# 2_ESP32.net
KiCad netlist of a schematic drawn in Altium Designer
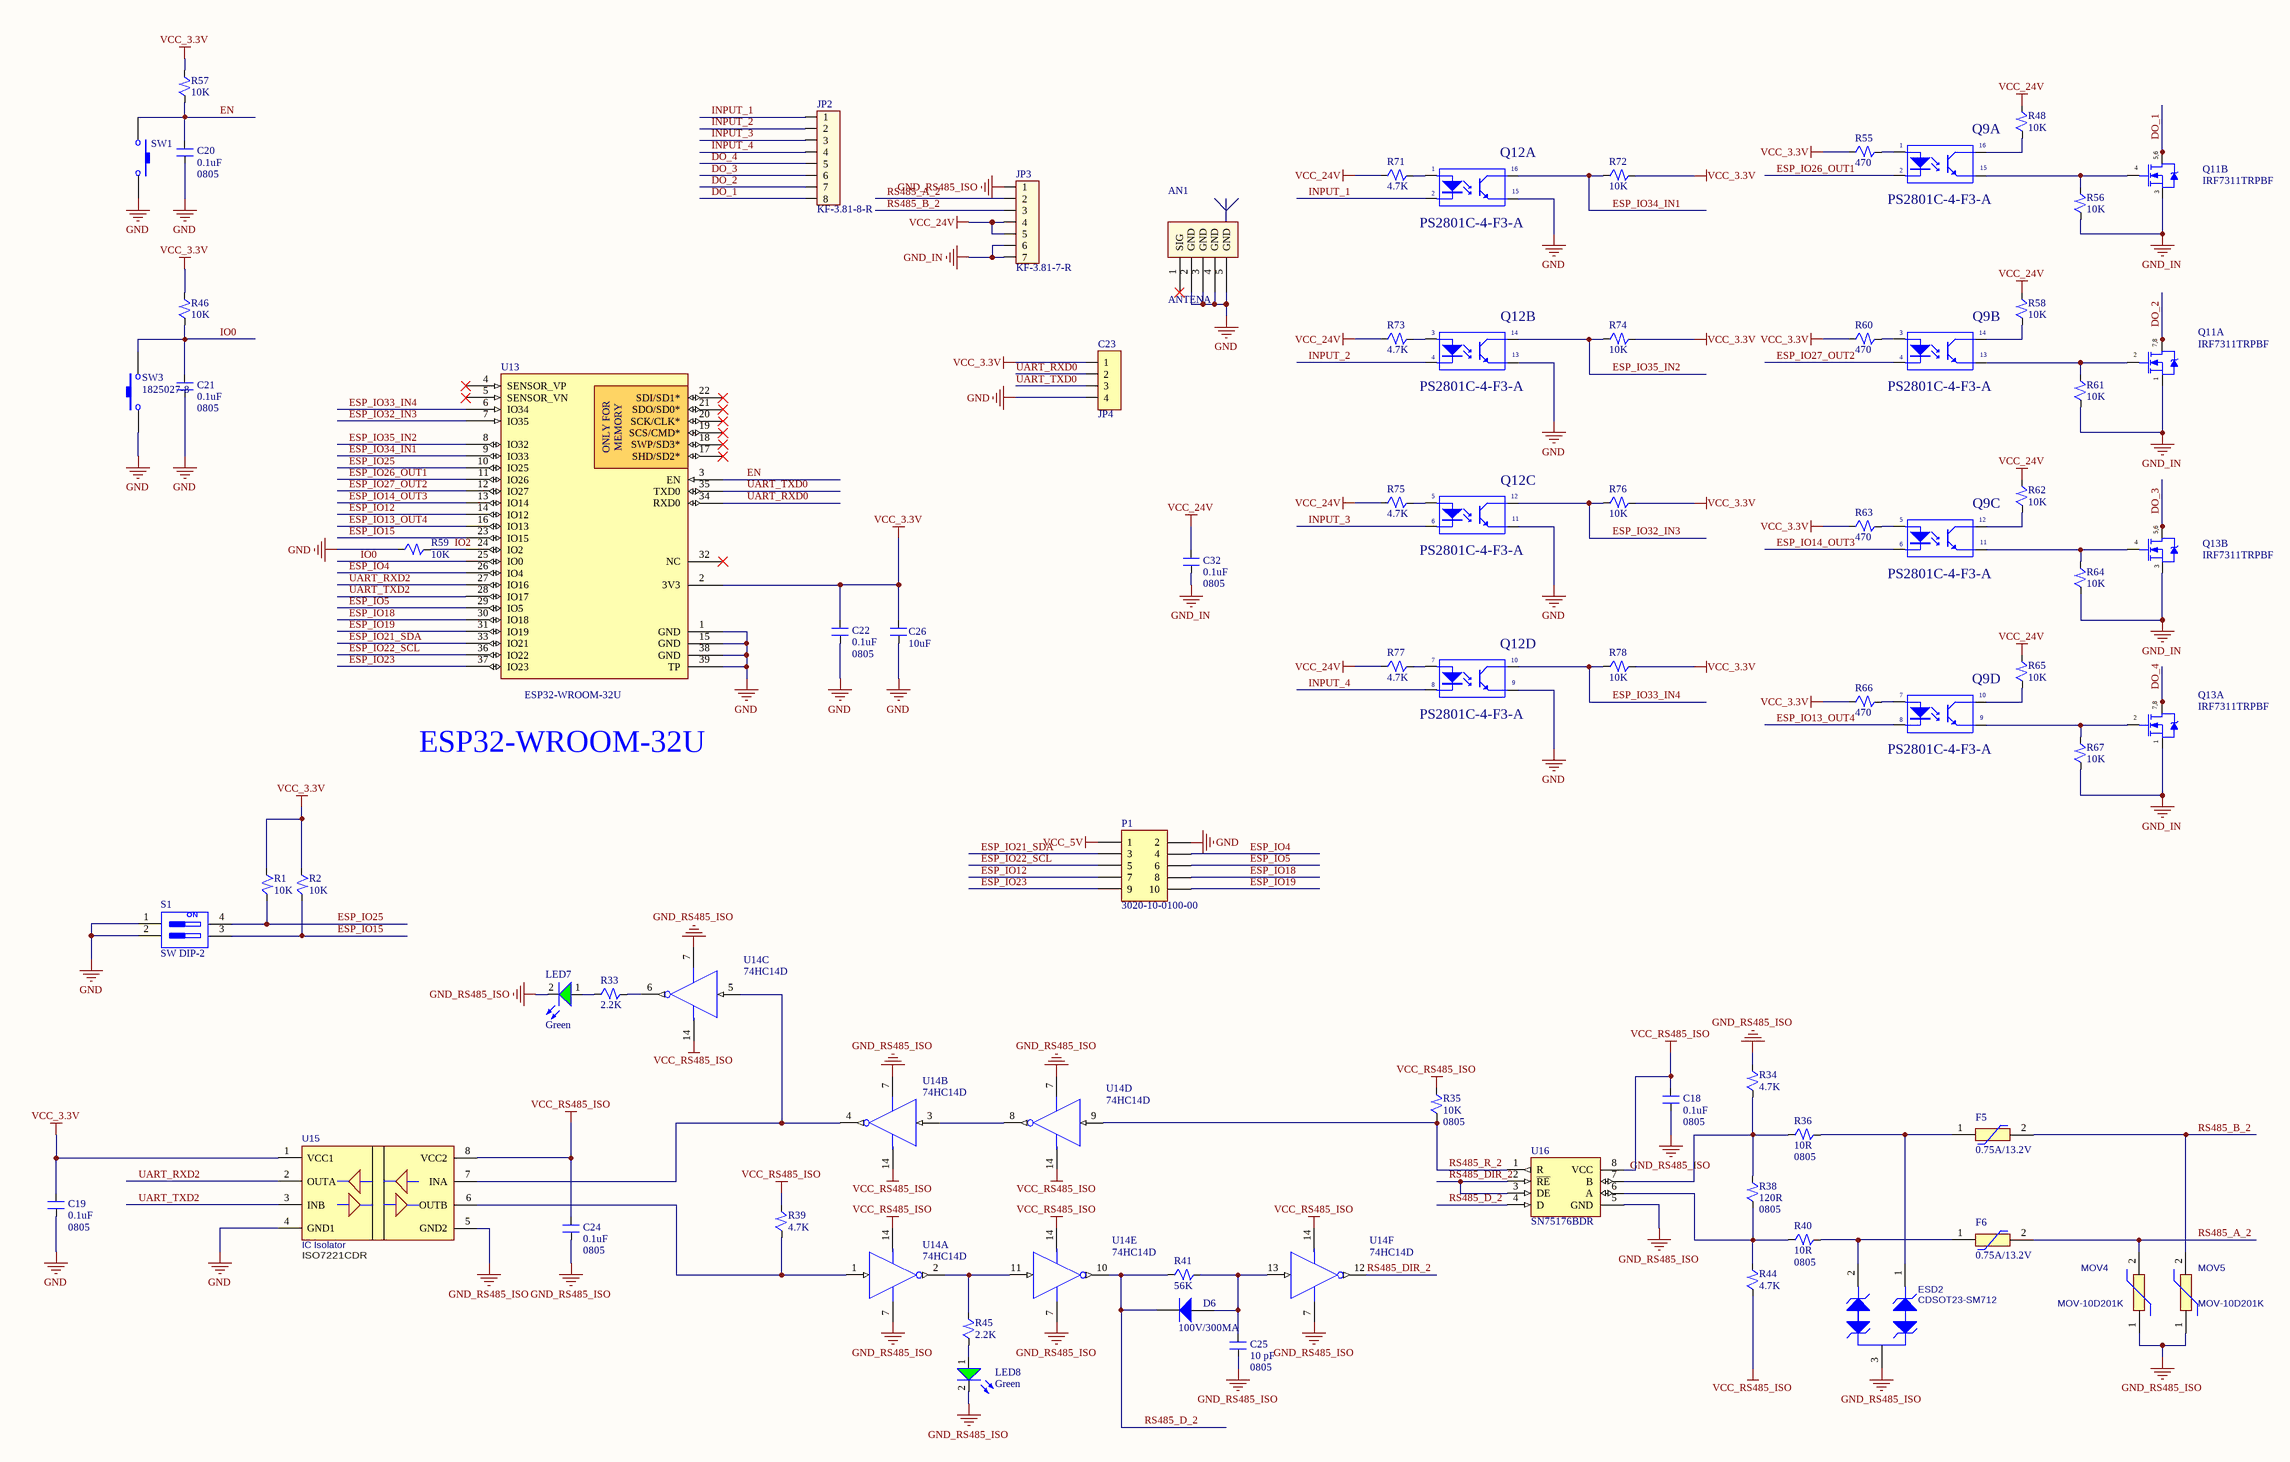
[diagram p0: [2] ESP32.SchDoc]

(export (version "E")
  (design (tool "Eeschema 10.0.6"))
  (components
    (comp (ref "AN1")
      (value "ANTENA")
      (footprint "DE ANTEN SMA CONG")
      (description "Generic Antenna")
      (libsource (lib "DIEN TU HELLO") (part "ANTEN SMA CONG"))
    )
    (comp (ref "C18")
      (value "0.1uF")
      (footprint "CN-SMD-0805")
      (description "CAP CER 0.1UF 50V 0805")
      (fields (field (name "PACKAGE") "0805") (field (name "TOLERANCE") "10%") (field (name "VOLTAGE") "50V"))
      (libsource (lib "DIEN TU HELLO") (part "CAP 0.1uF 0805 10% 50V"))
    )
    (comp (ref "C19")
      (value "0.1uF")
      (footprint "CN-SMD-0805")
      (description "CAP CER 0.1UF 50V 0805")
      (fields (field (name "PACKAGE") "0805") (field (name "TOLERANCE") "10%") (field (name "VOLTAGE") "50V"))
      (libsource (lib "DIEN TU HELLO") (part "CAP 0.1uF 0805 10% 50V"))
    )
    (comp (ref "C20")
      (value "0.1uF")
      (footprint "CN-SMD-0805")
      (description "CAP CER 0.1UF 50V 0805")
      (fields (field (name "PACKAGE") "0805") (field (name "TOLERANCE") "10%") (field (name "VOLTAGE") "50V"))
      (libsource (lib "DIEN TU HELLO") (part "CAP 0.1uF 0805 10% 50V"))
    )
    (comp (ref "C21")
      (value "0.1uF")
      (footprint "CN-SMD-0805")
      (description "CAP CER 0.1UF 50V 0805")
      (fields (field (name "PACKAGE") "0805") (field (name "TOLERANCE") "10%") (field (name "VOLTAGE") "50V"))
      (libsource (lib "DIEN TU HELLO") (part "CAP 0.1uF 0805 10% 50V"))
    )
    (comp (ref "C22")
      (value "0.1uF")
      (footprint "CN-SMD-0805")
      (description "CAP CER 0.1UF 50V 0805")
      (fields (field (name "PACKAGE") "0805") (field (name "TOLERANCE") "10%") (field (name "VOLTAGE") "50V"))
      (libsource (lib "DIEN TU HELLO") (part "CAP 0.1uF 0805 10% 50V"))
    )
    (comp (ref "C23")
      (value "JP4")
      (footprint "JP4-C1T")
      (description "WR-PHD 2.54 mm Angled Socket Header")
      (fields
        (field (name "MANUFACTURER") "Würth Elektronik eiSos GmbH")
        (field (name "PARTNO") "613004143121")
        (field (name "CREATED BY") "Karrer Zheng")
      )
      (libsource (lib "LIBRARY") (part "JP4"))
    )
    (comp (ref "C24")
      (value "0.1uF")
      (footprint "CN-SMD-0805")
      (description "CAP CER 0.1UF 50V 0805")
      (fields (field (name "PACKAGE") "0805") (field (name "TOLERANCE") "10%") (field (name "VOLTAGE") "50V"))
      (libsource (lib "DIEN TU HELLO") (part "CAP 0.1uF 0805 10% 50V"))
    )
    (comp (ref "C25")
      (value "10 pF")
      (footprint "CN-SMD-0805")
      (description "CAP CER 0.1UF 50V 0805")
      (fields (field (name "PACKAGE") "0805") (field (name "TOLERANCE") "10%") (field (name "VOLTAGE") "50V"))
      (libsource (lib "DIEN TU HELLO") (part "CAP 0.1uF 0805 10% 50V"))
    )
    (comp (ref "C26")
      (value "10uF")
      (footprint "CN-SMD-0805")
      (description "CAP CER 10UF 16V 0805")
      (fields (field (name "TOLERANCE") "10%") (field (name "VOLTAGE") "16V"))
      (libsource (lib "DIEN TU HELLO") (part "CAP 10uF 0805 10% 16V"))
    )
    (comp (ref "C32")
      (value "0.1uF")
      (footprint "CN-SMD-0805")
      (description "CAP CER 0.1UF 50V 0805")
      (fields (field (name "PACKAGE") "0805") (field (name "TOLERANCE") "10%") (field (name "VOLTAGE") "50V"))
      (libsource (lib "DIEN TU HELLO") (part "CAP 0.1uF 0805 10% 50V"))
    )
    (comp (ref "D6")
      (value "100V/300MA")
      (footprint "SOD-123")
      (description "DIODE GEN PURP 100V 300MA SOD123")
      (fields (field (name "PART NUMBER") "1N4148W-7-F") (field (name "MANUFACTURER") "Diodes Incorporated"))
      (libsource (lib "DIEN TU HELLO") (part "1N4148-W-7"))
    )
    (comp (ref "ESD2")
      (value "CDSOT23-SM712")
      (footprint "SOT-323_ESD")
      (fields (field (name "MANUFACTURER") "Bourns"))
      (libsource (lib "DIEN TU HELLO") (part "CDSOT23-SM712"))
    )
    (comp (ref "F5")
      (value "0.75A/13.2V")
      (footprint "MINISMDC050F2")
      (description "PTC RESET FUSE 13.2V 750MA 1812")
      (fields (field (name "MANUFACTURER") "LITTELFUSE") (field (name "PART NUMBER") "MINISMDC075F-2"))
      (libsource (lib "DIEN TU HELLO") (part "MINISMDC075F-2"))
    )
    (comp (ref "F6")
      (value "0.75A/13.2V")
      (footprint "MINISMDC050F2")
      (description "PTC RESET FUSE 13.2V 750MA 1812")
      (fields (field (name "MANUFACTURER") "LITTELFUSE") (field (name "PART NUMBER") "MINISMDC075F-2"))
      (libsource (lib "DIEN TU HELLO") (part "MINISMDC075F-2"))
    )
    (comp (ref "JP2")
      (value "KF-3.81-8-R")
      (footprint "KF-3.81-8-R")
      (description "Terminal Block Plug-in Hàn PCB Chân Cong 3.81mm")
      (libsource (lib "DIEN TU HELLO") (part "Con_8C"))
    )
    (comp (ref "JP3")
      (value "KF-3.81-7-R")
      (footprint "KF-3.81-7-R")
      (description "Terminal Block Plug-in Hàn PCB Chân Cong 3.81mm")
      (libsource (lib "DIEN TU HELLO") (part "Con_7C"))
    )
    (comp (ref "LED7")
      (value "Green")
      (footprint "LED5G")
      (description "LED Green 5mm")
      (fields (field (name "Comment") "LED_G_5"))
      (libsource (lib "DIEN TU HELLO") (part "LED_GREEN_5MM"))
    )
    (comp (ref "LED8")
      (value "Green")
      (footprint "LED5G")
      (description "LED Green 5mm")
      (fields (field (name "Comment") "LED_G_5"))
      (libsource (lib "DIEN TU HELLO") (part "LED_GREEN_5MM"))
    )
    (comp (ref "MOV4")
      (value "MOV-10D201K")
      (footprint "MOV10D201KTR")
      (description "MOV 225V 250pF 340V Clamp Voltage 2.5 kA 10%")
      (fields (field (name "MANUFACTURER") "Bourns"))
      (libsource (lib "DIEN TU HELLO") (part "MOV-10D201K"))
    )
    (comp (ref "MOV5")
      (value "MOV-10D201K")
      (footprint "MOV10D201KTR")
      (description "MOV 225V 250pF 340V Clamp Voltage 2.5 kA 10%")
      (fields (field (name "MANUFACTURER") "Bourns"))
      (libsource (lib "DIEN TU HELLO") (part "MOV-10D201K"))
    )
    (comp (ref "P1")
      (value "3020-10-0100-00")
      (footprint "IDC_HDR_M_2X5_2.54_THG")
      (description "IDC BOX HEADER .100\" 10POS")
      (fields (field (name "MANUFACTURER") "CNC Tech"))
      (libsource (lib "Indruino") (part "IDC_HDR_M_3020-10-0100-00"))
    )
    (comp (ref "Q9")
      (value "PS2801C-4-F3-A")
      (footprint "PS2801C-4_REN-L")
      (fields (field (name "MANUFACTURER") "Renesas Electronics"))
      (libsource (lib "DIEN TU HELLO") (part "PS2801C-4_MH"))
    )
    (comp (ref "Q11")
      (value "IRF7311TRPBF")
      (footprint "SO8")
      (description "MOSFET N-2CH 6.6A 20V 29mOhm 8-SOIC")
      (fields
        (field (name "MANUFACTURER") "Infineon Technologies")
        (field (name "PUBLISHER") "Altium Limited")
      )
      (libsource (lib "DIEN TU HELLO") (part "IRF7311TRPBF"))
    )
    (comp (ref "Q12")
      (value "PS2801C-4-F3-A")
      (footprint "PS2801C-4_REN-L")
      (fields (field (name "MANUFACTURER") "Renesas Electronics"))
      (libsource (lib "DIEN TU HELLO") (part "PS2801C-4_MH"))
    )
    (comp (ref "Q13")
      (value "IRF7311TRPBF")
      (footprint "SO8")
      (description "MOSFET N-2CH 6.6A 20V 29mOhm 8-SOIC")
      (fields
        (field (name "MANUFACTURER") "Infineon Technologies")
        (field (name "PUBLISHER") "Altium Limited")
      )
      (libsource (lib "DIEN TU HELLO") (part "IRF7311TRPBF"))
    )
    (comp (ref "R1")
      (value "10K")
      (footprint "RES_0805")
      (description "Điện Trở 10 KOhm 0805 1% 1/8W")
      (fields (field (name "PART NUMBER") "Trở 0805 1% 10K") (field (name "MANUFACTURER") "Minh Hà"))
      (libsource (lib "DIEN TU HELLO") (part "RES 10K 0805 1% 1/8W"))
    )
    (comp (ref "R2")
      (value "10K")
      (footprint "RES_0805")
      (description "Điện Trở 10 KOhm 0805 1% 1/8W")
      (fields (field (name "PART NUMBER") "Trở 0805 1% 10K") (field (name "MANUFACTURER") "Minh Hà"))
      (libsource (lib "DIEN TU HELLO") (part "RES 10K 0805 1% 1/8W"))
    )
    (comp (ref "R33")
      (value "2.2K")
      (footprint "RES_0805")
      (description "Điện Trở 2.2 KOhm 0805 1% 1/8W")
      (fields (field (name "PART NUMBER") "Trở 0805 1% 2.2K") (field (name "MANUFACTURER") "Minh Hà"))
      (libsource (lib "DIEN TU HELLO") (part "RES 2.2K 0805 1% 1/8W"))
    )
    (comp (ref "R34")
      (value "4.7K")
      (footprint "RES_0805")
      (description "Điện Trở 4.7 KOhm 0805 1% 1/8W")
      (fields (field (name "PART NUMBER") "Trở 0805 1% 4.7K") (field (name "MANUFACTURER") "Minh Hà"))
      (libsource (lib "DIEN TU HELLO") (part "RES 4.7K 0805 1% 1/8W"))
    )
    (comp (ref "R35")
      (value "10K")
      (footprint "RES_0805")
      (description "Điện Trở 10 KOhm 0805 1% 1/8W")
      (fields
        (field (name "PART NUMBER") "Trở 0805 1% 10K")
        (field (name "MANUFACTURER") "Minh Hà")
        (field (name "PACKAGE") "0805")
      )
      (libsource (lib "DIEN TU HELLO") (part "RES 10K 0805 1% 1/8W"))
    )
    (comp (ref "R36")
      (value "10R")
      (footprint "RES_0805")
      (description "Điện Trở 10 Ohm 0805 1% 1/8W")
      (fields
        (field (name "PART NUMBER") "Trở 0805 1% 10R")
        (field (name "MANUFACTURER") "Minh Hà")
        (field (name "PACKAGE") "0805")
      )
      (libsource (lib "DIEN TU HELLO") (part "RES 10R 0805 1% 1/8W"))
    )
    (comp (ref "R38")
      (value "120R")
      (footprint "RES_0805")
      (description "Điện Trở 120 Ohm 0805 1% 1/8W")
      (fields
        (field (name "PART NUMBER") "Trở 0805 1% 120R")
        (field (name "MANUFACTURER") "Minh Hà")
        (field (name "PACKAGE") "0805")
      )
      (libsource (lib "DIEN TU HELLO") (part "RES 120R 0805 1% 1/8W"))
    )
    (comp (ref "R39")
      (value "4.7K")
      (footprint "RES_0805")
      (description "Điện Trở 4.7 KOhm 0805 1% 1/8W")
      (fields (field (name "PART NUMBER") "Trở 0805 1% 4.7K") (field (name "MANUFACTURER") "Minh Hà"))
      (libsource (lib "DIEN TU HELLO") (part "RES 4.7K 0805 1% 1/8W"))
    )
    (comp (ref "R40")
      (value "10R")
      (footprint "RES_0805")
      (description "Điện Trở 10 Ohm 0805 1% 1/8W")
      (fields
        (field (name "PART NUMBER") "Trở 0805 1% 10R")
        (field (name "MANUFACTURER") "Minh Hà")
        (field (name "PACKAGE") "0805")
      )
      (libsource (lib "DIEN TU HELLO") (part "RES 10R 0805 1% 1/8W"))
    )
    (comp (ref "R41")
      (value "56K")
      (footprint "RES_0805")
      (description "Điện Trở 56 KOhm 0805 5% 1/8W")
      (fields (field (name "PART NUMBER") "Trở 0805 5% 56K") (field (name "MANUFACTURER") "Thế Giới IC"))
      (libsource (lib "DIEN TU HELLO") (part "RES 56K 0805 5% 1/8W"))
    )
    (comp (ref "R44")
      (value "4.7K")
      (footprint "RES_0805")
      (description "Điện Trở 4.7 KOhm 0805 1% 1/8W")
      (fields (field (name "PART NUMBER") "Trở 0805 1% 4.7K") (field (name "MANUFACTURER") "Minh Hà"))
      (libsource (lib "DIEN TU HELLO") (part "RES 4.7K 0805 1% 1/8W"))
    )
    (comp (ref "R45")
      (value "2.2K")
      (footprint "RES_0805")
      (description "Điện Trở 2.2 KOhm 0805 1% 1/8W")
      (fields (field (name "PART NUMBER") "Trở 0805 1% 2.2K") (field (name "MANUFACTURER") "Minh Hà"))
      (libsource (lib "DIEN TU HELLO") (part "RES 2.2K 0805 1% 1/8W"))
    )
    (comp (ref "R46")
      (value "10K")
      (footprint "RES_0805")
      (description "Điện Trở 10 KOhm 0805 1% 1/8W")
      (fields (field (name "PART NUMBER") "Trở 0805 1% 10K") (field (name "MANUFACTURER") "Minh Hà"))
      (libsource (lib "DIEN TU HELLO") (part "RES 10K 0805 1% 1/8W"))
    )
    (comp (ref "R48")
      (value "10K")
      (footprint "RES_0805")
      (description "Điện Trở 10 KOhm 0805 1% 1/8W")
      (fields (field (name "PART NUMBER") "Trở 0805 1% 10K") (field (name "MANUFACTURER") "Minh Hà"))
      (libsource (lib "DIEN TU HELLO") (part "RES 10K 0805 1% 1/8W"))
    )
    (comp (ref "R55")
      (value "470")
      (footprint "RES_0805")
      (description "Điện Trở 470 Ohm 0805 1% 1/8W")
      (fields (field (name "PART NUMBER") "Trở 0805 1% 470R") (field (name "MANUFACTURER") "Minh Hà"))
      (libsource (lib "DIEN TU HELLO") (part "RES 470R 0805 1% 1/8W"))
    )
    (comp (ref "R56")
      (value "10K")
      (footprint "RES_0805")
      (description "Điện Trở 10 KOhm 0805 1% 1/8W")
      (fields (field (name "PART NUMBER") "Trở 0805 1% 10K") (field (name "MANUFACTURER") "Minh Hà"))
      (libsource (lib "DIEN TU HELLO") (part "RES 10K 0805 1% 1/8W"))
    )
    (comp (ref "R57")
      (value "10K")
      (footprint "RES_0805")
      (description "Điện Trở 10 KOhm 0805 1% 1/8W")
      (fields (field (name "PART NUMBER") "Trở 0805 1% 10K") (field (name "MANUFACTURER") "Minh Hà"))
      (libsource (lib "DIEN TU HELLO") (part "RES 10K 0805 1% 1/8W"))
    )
    (comp (ref "R58")
      (value "10K")
      (footprint "RES_0805")
      (description "Điện Trở 10 KOhm 0805 1% 1/8W")
      (fields (field (name "PART NUMBER") "Trở 0805 1% 10K") (field (name "MANUFACTURER") "Minh Hà"))
      (libsource (lib "DIEN TU HELLO") (part "RES 10K 0805 1% 1/8W"))
    )
    (comp (ref "R59")
      (value "10K")
      (footprint "RES_0805")
      (description "Điện Trở 10 KOhm 0805 1% 1/8W")
      (fields (field (name "PART NUMBER") "Trở 0805 1% 10K") (field (name "MANUFACTURER") "Minh Hà"))
      (libsource (lib "DIEN TU HELLO") (part "RES 10K 0805 1% 1/8W"))
    )
    (comp (ref "R60")
      (value "470")
      (footprint "RES_0805")
      (description "Điện Trở 470 Ohm 0805 1% 1/8W")
      (fields (field (name "PART NUMBER") "Trở 0805 1% 470R") (field (name "MANUFACTURER") "Minh Hà"))
      (libsource (lib "DIEN TU HELLO") (part "RES 470R 0805 1% 1/8W"))
    )
    (comp (ref "R61")
      (value "10K")
      (footprint "RES_0805")
      (description "Điện Trở 10 KOhm 0805 1% 1/8W")
      (fields (field (name "PART NUMBER") "Trở 0805 1% 10K") (field (name "MANUFACTURER") "Minh Hà"))
      (libsource (lib "DIEN TU HELLO") (part "RES 10K 0805 1% 1/8W"))
    )
    (comp (ref "R62")
      (value "10K")
      (footprint "RES_0805")
      (description "Điện Trở 10 KOhm 0805 1% 1/8W")
      (fields (field (name "PART NUMBER") "Trở 0805 1% 10K") (field (name "MANUFACTURER") "Minh Hà"))
      (libsource (lib "DIEN TU HELLO") (part "RES 10K 0805 1% 1/8W"))
    )
    (comp (ref "R63")
      (value "470")
      (footprint "RES_0805")
      (description "Điện Trở 470 Ohm 0805 1% 1/8W")
      (fields (field (name "PART NUMBER") "Trở 0805 1% 470R") (field (name "MANUFACTURER") "Minh Hà"))
      (libsource (lib "DIEN TU HELLO") (part "RES 470R 0805 1% 1/8W"))
    )
    (comp (ref "R64")
      (value "10K")
      (footprint "RES_0805")
      (description "Điện Trở 10 KOhm 0805 1% 1/8W")
      (fields (field (name "PART NUMBER") "Trở 0805 1% 10K") (field (name "MANUFACTURER") "Minh Hà"))
      (libsource (lib "DIEN TU HELLO") (part "RES 10K 0805 1% 1/8W"))
    )
    (comp (ref "R65")
      (value "10K")
      (footprint "RES_0805")
      (description "Điện Trở 10 KOhm 0805 1% 1/8W")
      (fields (field (name "PART NUMBER") "Trở 0805 1% 10K") (field (name "MANUFACTURER") "Minh Hà"))
      (libsource (lib "DIEN TU HELLO") (part "RES 10K 0805 1% 1/8W"))
    )
    (comp (ref "R66")
      (value "470")
      (footprint "RES_0805")
      (description "Điện Trở 470 Ohm 0805 1% 1/8W")
      (fields (field (name "PART NUMBER") "Trở 0805 1% 470R") (field (name "MANUFACTURER") "Minh Hà"))
      (libsource (lib "DIEN TU HELLO") (part "RES 470R 0805 1% 1/8W"))
    )
    (comp (ref "R67")
      (value "10K")
      (footprint "RES_0805")
      (description "Điện Trở 10 KOhm 0805 1% 1/8W")
      (fields (field (name "PART NUMBER") "Trở 0805 1% 10K") (field (name "MANUFACTURER") "Minh Hà"))
      (libsource (lib "DIEN TU HELLO") (part "RES 10K 0805 1% 1/8W"))
    )
    (comp (ref "R71")
      (value "4.7K")
      (footprint "RES_0805")
      (description "Điện Trở 4.7 KOhm 0805 1% 1/8W")
      (fields (field (name "PART NUMBER") "Trở 0805 1% 4.7K") (field (name "MANUFACTURER") "Minh Hà"))
      (libsource (lib "DIEN TU HELLO") (part "RES 4.7K 0805 1% 1/8W"))
    )
    (comp (ref "R72")
      (value "10K")
      (footprint "RES_0805")
      (description "Điện Trở 10 KOhm 0805 1% 1/8W")
      (fields (field (name "PART NUMBER") "Trở 0805 1% 10K") (field (name "MANUFACTURER") "Minh Hà"))
      (libsource (lib "DIEN TU HELLO") (part "RES 10K 0805 1% 1/8W"))
    )
    (comp (ref "R73")
      (value "4.7K")
      (footprint "RES_0805")
      (description "Điện Trở 4.7 KOhm 0805 1% 1/8W")
      (fields (field (name "PART NUMBER") "Trở 0805 1% 4.7K") (field (name "MANUFACTURER") "Minh Hà"))
      (libsource (lib "DIEN TU HELLO") (part "RES 4.7K 0805 1% 1/8W"))
    )
    (comp (ref "R74")
      (value "10K")
      (footprint "RES_0805")
      (description "Điện Trở 10 KOhm 0805 1% 1/8W")
      (fields (field (name "PART NUMBER") "Trở 0805 1% 10K") (field (name "MANUFACTURER") "Minh Hà"))
      (libsource (lib "DIEN TU HELLO") (part "RES 10K 0805 1% 1/8W"))
    )
    (comp (ref "R75")
      (value "4.7K")
      (footprint "RES_0805")
      (description "Điện Trở 4.7 KOhm 0805 1% 1/8W")
      (fields (field (name "PART NUMBER") "Trở 0805 1% 4.7K") (field (name "MANUFACTURER") "Minh Hà"))
      (libsource (lib "DIEN TU HELLO") (part "RES 4.7K 0805 1% 1/8W"))
    )
    (comp (ref "R76")
      (value "10K")
      (footprint "RES_0805")
      (description "Điện Trở 10 KOhm 0805 1% 1/8W")
      (fields (field (name "PART NUMBER") "Trở 0805 1% 10K") (field (name "MANUFACTURER") "Minh Hà"))
      (libsource (lib "DIEN TU HELLO") (part "RES 10K 0805 1% 1/8W"))
    )
    (comp (ref "R77")
      (value "4.7K")
      (footprint "RES_0805")
      (description "Điện Trở 4.7 KOhm 0805 1% 1/8W")
      (fields (field (name "PART NUMBER") "Trở 0805 1% 4.7K") (field (name "MANUFACTURER") "Minh Hà"))
      (libsource (lib "DIEN TU HELLO") (part "RES 4.7K 0805 1% 1/8W"))
    )
    (comp (ref "R78")
      (value "10K")
      (footprint "RES_0805")
      (description "Điện Trở 10 KOhm 0805 1% 1/8W")
      (fields (field (name "PART NUMBER") "Trở 0805 1% 10K") (field (name "MANUFACTURER") "Minh Hà"))
      (libsource (lib "DIEN TU HELLO") (part "RES 10K 0805 1% 1/8W"))
    )
    (comp (ref "S1")
      (value "SW DIP-2")
      (footprint "MinhTien_PCBLib:DIP-SW-2-SIDE ENTRY")
      (description "DIP Switch, 2 Position, SPST")
      (fields (field (name "PUBLISHER") "Altium Limited"))
      (libsource (lib "MinhTien_SCHLib") (part "SW DIP-2"))
    )
    (comp (ref "SW1")
      (value "RS-282G05A3-SM RT")
      (footprint "SW_RS-282G05A3-SM RT")
      (description "SWITCH TACTILE SPST-NO 0.05A 12V")
      (fields (field (name "MANUFACTURER") "C&K"))
      (libsource (lib "DIEN TU HELLO") (part "SW_RS-282G05A3-SM RT"))
    )
    (comp (ref "SW3")
      (value "1825027-8")
      (footprint "SW_1825027-8")
      (description "SWITCH TACTILE SPST-NO 0.05A 24V")
      (fields (field (name "MANUFACTURER") "TE Connectivity ALCOSWITCH Switches"))
      (libsource (lib "Indruino") (part "SW_1825027-8"))
    )
    (comp (ref "U13")
      (value "ESP32-WROOM-32U")
      (footprint "ESP32-WROOM-32U")
      (description "Wi-Fi/BT BLE Module ESP32-D0WD")
      (fields (field (name "MANUFACTURER") "Espressif"))
      (libsource (lib "DIEN TU HELLO") (part "ESP32-WROOM-32U"))
    )
    (comp (ref "U14")
      (value "74HC14D")
      (footprint "SOIC-14")
      (description "IC INVERTER SCHMITT TRIGGER 6CH 6-INP")
      (fields (field (name "MANUFACTURER") "Nexperia USA Inc") (field (name "BASE PART NUMBER") "74HC14"))
      (libsource (lib "") (part "74HC14D_NXP_1"))
    )
    (comp (ref "U15")
      (value "IC Isolator")
      (footprint "8-SOIC_ISO")
      (description "IC Isolator 2.8V ~ 5.5V 2 Channels 25Mbps")
      (fields (field (name "MANUFACTURER") "Texas Instruments") (field (name "PART NUMBER") "ISO7221CDR"))
      (libsource (lib "DIEN TU HELLO") (part "ISO7221CD"))
    )
    (comp (ref "U16")
      (value "SN75176BDR")
      (footprint "SOIC-8")
      (description "IC TXRX DIFF BUSS 8SOIC")
      (fields (field (name "MANUFACTURER") "Texas Instruments") (field (name "PART NUMBER") "SN75HVD08DR"))
      (libsource (lib "DIEN TU HELLO") (part "SN75176BDR"))
    )
  )
  (nets
    (net (code "1") (name "/DO_1") (class "Default")
      (node (ref "JP2") (pin "8") (pinfunction "8_8") (pintype "passive"))
      (node (ref "Q11") (pin "5") (pinfunction "D_5") (pintype "passive"))
      (node (ref "Q11") (pin "6") (pinfunction "D_6") (pintype "passive"))
    )
    (net (code "2") (name "/DO_2") (class "Default")
      (node (ref "JP2") (pin "7") (pinfunction "7_7") (pintype "passive"))
      (node (ref "Q11") (pin "7") (pinfunction "D_7") (pintype "passive"))
      (node (ref "Q11") (pin "8") (pinfunction "D_8") (pintype "passive"))
    )
    (net (code "3") (name "/DO_3") (class "Default")
      (node (ref "JP2") (pin "6") (pinfunction "6_6") (pintype "passive"))
      (node (ref "Q13") (pin "5") (pinfunction "D_5") (pintype "passive"))
      (node (ref "Q13") (pin "6") (pinfunction "D_6") (pintype "passive"))
    )
    (net (code "4") (name "/DO_4") (class "Default")
      (node (ref "JP2") (pin "5") (pinfunction "5_5") (pintype "passive"))
      (node (ref "Q13") (pin "7") (pinfunction "D_7") (pintype "passive"))
      (node (ref "Q13") (pin "8") (pinfunction "D_8") (pintype "passive"))
    )
    (net (code "5") (name "/EN") (class "Default")
      (node (ref "C20") (pin "2") (pinfunction "2_2") (pintype "passive"))
      (node (ref "R57") (pin "1") (pinfunction "1_1") (pintype "passive"))
      (node (ref "SW1") (pin "1") (pinfunction "1_1") (pintype "passive"))
      (node (ref "U13") (pin "3") (pinfunction "EN_3") (pintype "input"))
    )
    (net (code "6") (name "/ESP_IO4") (class "Default")
      (node (ref "P1") (pin "4") (pinfunction "4_4") (pintype "passive"))
      (node (ref "U13") (pin "26") (pinfunction "IO4_26") (pintype "bidirectional"))
    )
    (net (code "7") (name "/ESP_IO5") (class "Default")
      (node (ref "P1") (pin "6") (pinfunction "6_6") (pintype "passive"))
      (node (ref "U13") (pin "29") (pinfunction "IO5_29") (pintype "bidirectional"))
    )
    (net (code "8") (name "/ESP_IO12") (class "Default")
      (node (ref "P1") (pin "7") (pinfunction "7_7") (pintype "passive"))
      (node (ref "U13") (pin "14") (pinfunction "IO12_14") (pintype "bidirectional"))
    )
    (net (code "9") (name "/ESP_IO13_OUT4") (class "Default")
      (node (ref "Q9") (pin "8") (pinfunction "8_8") (pintype "passive"))
      (node (ref "U13") (pin "16") (pinfunction "IO13_16") (pintype "bidirectional"))
    )
    (net (code "10") (name "/ESP_IO14_OUT3") (class "Default")
      (node (ref "Q9") (pin "6") (pinfunction "6_6") (pintype "passive"))
      (node (ref "U13") (pin "13") (pinfunction "IO14_13") (pintype "bidirectional"))
    )
    (net (code "11") (name "/ESP_IO15") (class "Default")
      (node (ref "R2") (pin "2") (pinfunction "2_2") (pintype "passive"))
      (node (ref "S1") (pin "3") (pinfunction "B2_3") (pintype "passive"))
      (node (ref "U13") (pin "23") (pinfunction "IO15_23") (pintype "bidirectional"))
    )
    (net (code "12") (name "/ESP_IO18") (class "Default")
      (node (ref "P1") (pin "8") (pinfunction "8_8") (pintype "passive"))
      (node (ref "U13") (pin "30") (pinfunction "IO18_30") (pintype "bidirectional"))
    )
    (net (code "13") (name "/ESP_IO19") (class "Default")
      (node (ref "P1") (pin "10") (pinfunction "10_10") (pintype "passive"))
      (node (ref "U13") (pin "31") (pinfunction "IO19_31") (pintype "bidirectional"))
    )
    (net (code "14") (name "/ESP_IO21_SDA") (class "Default")
      (node (ref "P1") (pin "3") (pinfunction "3_3") (pintype "passive"))
      (node (ref "U13") (pin "33") (pinfunction "IO21_33") (pintype "bidirectional"))
    )
    (net (code "15") (name "/ESP_IO22_SCL") (class "Default")
      (node (ref "P1") (pin "5") (pinfunction "5_5") (pintype "passive"))
      (node (ref "U13") (pin "36") (pinfunction "IO22_36") (pintype "bidirectional"))
    )
    (net (code "16") (name "/ESP_IO23") (class "Default")
      (node (ref "P1") (pin "9") (pinfunction "9_9") (pintype "passive"))
      (node (ref "U13") (pin "37") (pinfunction "IO23_37") (pintype "bidirectional"))
    )
    (net (code "17") (name "/ESP_IO25") (class "Default")
      (node (ref "R1") (pin "2") (pinfunction "2_2") (pintype "passive"))
      (node (ref "S1") (pin "4") (pinfunction "B1_4") (pintype "passive"))
      (node (ref "U13") (pin "10") (pinfunction "IO25_10") (pintype "bidirectional"))
    )
    (net (code "18") (name "/ESP_IO26_OUT1") (class "Default")
      (node (ref "Q9") (pin "2") (pinfunction "2_2") (pintype "passive"))
      (node (ref "U13") (pin "11") (pinfunction "IO26_11") (pintype "bidirectional"))
    )
    (net (code "19") (name "/ESP_IO27_OUT2") (class "Default")
      (node (ref "Q9") (pin "4") (pinfunction "4_4") (pintype "passive"))
      (node (ref "U13") (pin "12") (pinfunction "IO27_12") (pintype "bidirectional"))
    )
    (net (code "20") (name "/ESP_IO32_IN3") (class "Default")
      (node (ref "Q12") (pin "12") (pinfunction "12_12") (pintype "passive"))
      (node (ref "R76") (pin "1") (pinfunction "1_1") (pintype "passive"))
      (node (ref "U13") (pin "7") (pinfunction "IO35_7") (pintype "input"))
    )
    (net (code "21") (name "/ESP_IO33_IN4") (class "Default")
      (node (ref "Q12") (pin "10") (pinfunction "10_10") (pintype "passive"))
      (node (ref "R78") (pin "1") (pinfunction "1_1") (pintype "passive"))
      (node (ref "U13") (pin "6") (pinfunction "IO34_6") (pintype "input"))
    )
    (net (code "22") (name "/ESP_IO34_IN1") (class "Default")
      (node (ref "Q12") (pin "16") (pinfunction "16_16") (pintype "passive"))
      (node (ref "R72") (pin "1") (pinfunction "1_1") (pintype "passive"))
      (node (ref "U13") (pin "9") (pinfunction "IO33_9") (pintype "bidirectional"))
    )
    (net (code "23") (name "/ESP_IO35_IN2") (class "Default")
      (node (ref "Q12") (pin "14") (pinfunction "14_14") (pintype "passive"))
      (node (ref "R74") (pin "1") (pinfunction "1_1") (pintype "passive"))
      (node (ref "U13") (pin "8") (pinfunction "IO32_8") (pintype "bidirectional"))
    )
    (net (code "24") (name "/INPUT_1") (class "Default")
      (node (ref "JP2") (pin "1") (pinfunction "1_1") (pintype "passive"))
      (node (ref "Q12") (pin "2") (pinfunction "2_2") (pintype "passive"))
    )
    (net (code "25") (name "/INPUT_2") (class "Default")
      (node (ref "JP2") (pin "2") (pinfunction "2_2") (pintype "passive"))
      (node (ref "Q12") (pin "4") (pinfunction "4_4") (pintype "passive"))
    )
    (net (code "26") (name "/INPUT_3") (class "Default")
      (node (ref "JP2") (pin "3") (pinfunction "3_3") (pintype "passive"))
      (node (ref "Q12") (pin "6") (pinfunction "6_6") (pintype "passive"))
    )
    (net (code "27") (name "/INPUT_4") (class "Default")
      (node (ref "JP2") (pin "4") (pinfunction "4_4") (pintype "passive"))
      (node (ref "Q12") (pin "8") (pinfunction "8_8") (pintype "passive"))
    )
    (net (code "28") (name "/IO0") (class "Default")
      (node (ref "C21") (pin "2") (pinfunction "2_2") (pintype "passive"))
      (node (ref "R46") (pin "1") (pinfunction "1_1") (pintype "passive"))
      (node (ref "SW3") (pin "2") (pinfunction "2_2") (pintype "passive"))
      (node (ref "U13") (pin "25") (pinfunction "IO0_25") (pintype "bidirectional"))
    )
    (net (code "29") (name "/IO2") (class "Default")
      (node (ref "R59") (pin "2") (pinfunction "2_2") (pintype "passive"))
      (node (ref "U13") (pin "24") (pinfunction "IO2_24") (pintype "bidirectional"))
    )
    (net (code "30") (name "/RS485_A_2") (class "Default")
      (node (ref "F6") (pin "2") (pinfunction "2_2") (pintype "passive"))
      (node (ref "JP3") (pin "2") (pinfunction "2_2") (pintype "passive"))
      (node (ref "MOV4") (pin "2") (pinfunction "2_2") (pintype "passive"))
    )
    (net (code "31") (name "/RS485_B_2") (class "Default")
      (node (ref "F5") (pin "2") (pinfunction "2_2") (pintype "passive"))
      (node (ref "JP3") (pin "3") (pinfunction "3_3") (pintype "passive"))
      (node (ref "MOV5") (pin "2") (pinfunction "2_2") (pintype "passive"))
    )
    (net (code "32") (name "/RS485_DIR_2") (class "Default")
      (node (ref "U14") (pin "12") (pinfunction "6Y_12") (pintype "output"))
      (node (ref "U16") (pin "2") (pinfunction "~{RE}_2") (pintype "input"))
      (node (ref "U16") (pin "3") (pinfunction "DE_3") (pintype "input"))
    )
    (net (code "33") (name "/RS485_D_2") (class "Default")
      (node (ref "D6") (pin "2") (pinfunction "K_2") (pintype "passive"))
      (node (ref "R41") (pin "1") (pinfunction "1_1") (pintype "passive"))
      (node (ref "U14") (pin "10") (pinfunction "5Y_10") (pintype "output"))
      (node (ref "U16") (pin "4") (pinfunction "D_4") (pintype "input"))
    )
    (net (code "34") (name "/RS485_R_2") (class "Default")
      (node (ref "R35") (pin "1") (pinfunction "1_1") (pintype "passive"))
      (node (ref "U14") (pin "9") (pinfunction "4A_9") (pintype "input"))
      (node (ref "U16") (pin "1") (pinfunction "R_1") (pintype "output"))
    )
    (net (code "35") (name "/UART_RXD0") (class "Default")
      (node (ref "C23") (pin "2") (pinfunction "2_2") (pintype "passive"))
      (node (ref "U13") (pin "34") (pinfunction "RXD0_34") (pintype "bidirectional"))
    )
    (net (code "36") (name "/UART_RXD2") (class "Default")
      (node (ref "U13") (pin "27") (pinfunction "IO16_27") (pintype "bidirectional"))
      (node (ref "U15") (pin "2") (pinfunction "OUTA_2") (pintype "passive"))
    )
    (net (code "37") (name "/UART_TXD0") (class "Default")
      (node (ref "C23") (pin "3") (pinfunction "3_3") (pintype "passive"))
      (node (ref "U13") (pin "35") (pinfunction "TXD0_35") (pintype "bidirectional"))
    )
    (net (code "38") (name "/UART_TXD2") (class "Default")
      (node (ref "U13") (pin "28") (pinfunction "IO17_28") (pintype "bidirectional"))
      (node (ref "U15") (pin "3") (pinfunction "INB_3") (pintype "passive"))
    )
    (net (code "39") (name "GND") (class "Default")
      (node (ref "AN1") (pin "2") (pinfunction "GND_2") (pintype "passive"))
      (node (ref "AN1") (pin "3") (pinfunction "GND_3") (pintype "passive"))
      (node (ref "AN1") (pin "4") (pinfunction "GND_4") (pintype "passive"))
      (node (ref "AN1") (pin "5") (pinfunction "GND_5") (pintype "passive"))
      (node (ref "C19") (pin "1") (pinfunction "1_1") (pintype "passive"))
      (node (ref "C20") (pin "1") (pinfunction "1_1") (pintype "passive"))
      (node (ref "C21") (pin "1") (pinfunction "1_1") (pintype "passive"))
      (node (ref "C22") (pin "1") (pinfunction "1_1") (pintype "passive"))
      (node (ref "C23") (pin "4") (pinfunction "4_4") (pintype "passive"))
      (node (ref "C26") (pin "1") (pinfunction "1_1") (pintype "passive"))
      (node (ref "P1") (pin "2") (pinfunction "2_2") (pintype "passive"))
      (node (ref "Q12") (pin "11") (pinfunction "11_11") (pintype "passive"))
      (node (ref "Q12") (pin "13") (pinfunction "13_13") (pintype "passive"))
      (node (ref "Q12") (pin "15") (pinfunction "15_15") (pintype "passive"))
      (node (ref "Q12") (pin "9") (pinfunction "9_9") (pintype "passive"))
      (node (ref "R59") (pin "1") (pinfunction "1_1") (pintype "passive"))
      (node (ref "S1") (pin "1") (pinfunction "A1_1") (pintype "passive"))
      (node (ref "S1") (pin "2") (pinfunction "A2_2") (pintype "passive"))
      (node (ref "SW1") (pin "2") (pinfunction "2_2") (pintype "passive"))
      (node (ref "SW3") (pin "1") (pinfunction "1_1") (pintype "passive"))
      (node (ref "U13") (pin "1") (pinfunction "GND_1") (pintype "power_in"))
      (node (ref "U13") (pin "15") (pinfunction "GND_15") (pintype "power_in"))
      (node (ref "U13") (pin "38") (pinfunction "GND_38") (pintype "power_in"))
      (node (ref "U13") (pin "39") (pinfunction "TP_39") (pintype "power_in"))
      (node (ref "U15") (pin "4") (pinfunction "GND1_4") (pintype "passive"))
    )
    (net (code "40") (name "GND_IN") (class "Default")
      (node (ref "C32") (pin "1") (pinfunction "1_1") (pintype "passive"))
      (node (ref "JP3") (pin "6") (pinfunction "6_6") (pintype "passive"))
      (node (ref "JP3") (pin "7") (pinfunction "7_7") (pintype "passive"))
      (node (ref "Q11") (pin "1") (pinfunction "S_1") (pintype "passive"))
      (node (ref "Q11") (pin "3") (pinfunction "S_3") (pintype "passive"))
      (node (ref "Q13") (pin "1") (pinfunction "S_1") (pintype "passive"))
      (node (ref "Q13") (pin "3") (pinfunction "S_3") (pintype "passive"))
      (node (ref "R56") (pin "1") (pinfunction "1_1") (pintype "passive"))
      (node (ref "R61") (pin "1") (pinfunction "1_1") (pintype "passive"))
      (node (ref "R64") (pin "1") (pinfunction "1_1") (pintype "passive"))
      (node (ref "R67") (pin "1") (pinfunction "1_1") (pintype "passive"))
    )
    (net (code "41") (name "GND_RS485_ISO") (class "Default")
      (node (ref "C18") (pin "1") (pinfunction "1_1") (pintype "passive"))
      (node (ref "C24") (pin "1") (pinfunction "1_1") (pintype "passive"))
      (node (ref "C25") (pin "1") (pinfunction "1_1") (pintype "passive"))
      (node (ref "ESD2") (pin "3") (pinfunction "A_3") (pintype "passive"))
      (node (ref "JP3") (pin "1") (pinfunction "1_1") (pintype "passive"))
      (node (ref "LED7") (pin "2") (pinfunction "K_2") (pintype "passive"))
      (node (ref "LED8") (pin "2") (pinfunction "K_2") (pintype "passive"))
      (node (ref "MOV4") (pin "1") (pinfunction "1_1") (pintype "passive"))
      (node (ref "MOV5") (pin "1") (pinfunction "1_1") (pintype "passive"))
      (node (ref "R34") (pin "2") (pinfunction "2_2") (pintype "passive"))
      (node (ref "U14") (pin "7") (pinfunction "GND_7") (pintype "power_in"))
      (node (ref "U15") (pin "5") (pinfunction "GND2_5") (pintype "passive"))
      (node (ref "U16") (pin "5") (pinfunction "GND_5") (pintype "power_in"))
    )
    (net (code "42") (name "Net-(D6-A)") (class "Default")
      (node (ref "C25") (pin "2") (pinfunction "2_2") (pintype "passive"))
      (node (ref "D6") (pin "1") (pinfunction "A_1") (pintype "passive"))
      (node (ref "R41") (pin "2") (pinfunction "2_2") (pintype "passive"))
      (node (ref "U14") (pin "13") (pinfunction "6A_13") (pintype "input"))
    )
    (net (code "43") (name "Net-(ESD2-K-Pad1)") (class "Default")
      (node (ref "ESD2") (pin "1") (pinfunction "K_1") (pintype "passive"))
      (node (ref "F5") (pin "1") (pinfunction "1_1") (pintype "passive"))
      (node (ref "R36") (pin "2") (pinfunction "2_2") (pintype "passive"))
    )
    (net (code "44") (name "Net-(ESD2-K-Pad2)") (class "Default")
      (node (ref "ESD2") (pin "2") (pinfunction "K_2") (pintype "passive"))
      (node (ref "F6") (pin "1") (pinfunction "1_1") (pintype "passive"))
      (node (ref "R40") (pin "2") (pinfunction "2_2") (pintype "passive"))
    )
    (net (code "45") (name "Net-(LED7-A)") (class "Default")
      (node (ref "LED7") (pin "1") (pinfunction "A_1") (pintype "passive"))
      (node (ref "R33") (pin "1") (pinfunction "1_1") (pintype "passive"))
    )
    (net (code "46") (name "Net-(LED8-A)") (class "Default")
      (node (ref "LED8") (pin "1") (pinfunction "A_1") (pintype "passive"))
      (node (ref "R45") (pin "1") (pinfunction "1_1") (pintype "passive"))
    )
    (net (code "47") (name "Net-(Q9-Pad1)") (class "Default")
      (node (ref "Q9") (pin "1") (pinfunction "1_1") (pintype "passive"))
      (node (ref "R55") (pin "2") (pinfunction "2_2") (pintype "passive"))
    )
    (net (code "48") (name "Net-(Q9-Pad3)") (class "Default")
      (node (ref "Q9") (pin "3") (pinfunction "3_3") (pintype "passive"))
      (node (ref "R60") (pin "2") (pinfunction "2_2") (pintype "passive"))
    )
    (net (code "49") (name "Net-(Q9-Pad5)") (class "Default")
      (node (ref "Q9") (pin "5") (pinfunction "5_5") (pintype "passive"))
      (node (ref "R63") (pin "2") (pinfunction "2_2") (pintype "passive"))
    )
    (net (code "50") (name "Net-(Q9-Pad7)") (class "Default")
      (node (ref "Q9") (pin "7") (pinfunction "7_7") (pintype "passive"))
      (node (ref "R66") (pin "2") (pinfunction "2_2") (pintype "passive"))
    )
    (net (code "51") (name "Net-(Q9-Pad10)") (class "Default")
      (node (ref "Q9") (pin "10") (pinfunction "10_10") (pintype "passive"))
      (node (ref "R65") (pin "1") (pinfunction "1_1") (pintype "passive"))
    )
    (net (code "52") (name "Net-(Q9-Pad12)") (class "Default")
      (node (ref "Q9") (pin "12") (pinfunction "12_12") (pintype "passive"))
      (node (ref "R62") (pin "1") (pinfunction "1_1") (pintype "passive"))
    )
    (net (code "53") (name "Net-(Q9-Pad14)") (class "Default")
      (node (ref "Q9") (pin "14") (pinfunction "14_14") (pintype "passive"))
      (node (ref "R58") (pin "1") (pinfunction "1_1") (pintype "passive"))
    )
    (net (code "54") (name "Net-(Q9-Pad16)") (class "Default")
      (node (ref "Q9") (pin "16") (pinfunction "16_16") (pintype "passive"))
      (node (ref "R48") (pin "1") (pinfunction "1_1") (pintype "passive"))
    )
    (net (code "55") (name "Net-(Q11A-G)") (class "Default")
      (node (ref "Q11") (pin "2") (pinfunction "G_2") (pintype "passive"))
      (node (ref "Q9") (pin "13") (pinfunction "13_13") (pintype "passive"))
      (node (ref "R61") (pin "2") (pinfunction "2_2") (pintype "passive"))
    )
    (net (code "56") (name "Net-(Q11B-G)") (class "Default")
      (node (ref "Q11") (pin "4") (pinfunction "G_4") (pintype "passive"))
      (node (ref "Q9") (pin "15") (pinfunction "15_15") (pintype "passive"))
      (node (ref "R56") (pin "2") (pinfunction "2_2") (pintype "passive"))
    )
    (net (code "57") (name "Net-(Q12-Pad1)") (class "Default")
      (node (ref "Q12") (pin "1") (pinfunction "1_1") (pintype "passive"))
      (node (ref "R71") (pin "2") (pinfunction "2_2") (pintype "passive"))
    )
    (net (code "58") (name "Net-(Q12-Pad3)") (class "Default")
      (node (ref "Q12") (pin "3") (pinfunction "3_3") (pintype "passive"))
      (node (ref "R73") (pin "2") (pinfunction "2_2") (pintype "passive"))
    )
    (net (code "59") (name "Net-(Q12-Pad5)") (class "Default")
      (node (ref "Q12") (pin "5") (pinfunction "5_5") (pintype "passive"))
      (node (ref "R75") (pin "2") (pinfunction "2_2") (pintype "passive"))
    )
    (net (code "60") (name "Net-(Q12-Pad7)") (class "Default")
      (node (ref "Q12") (pin "7") (pinfunction "7_7") (pintype "passive"))
      (node (ref "R77") (pin "2") (pinfunction "2_2") (pintype "passive"))
    )
    (net (code "61") (name "Net-(Q13A-G)") (class "Default")
      (node (ref "Q13") (pin "2") (pinfunction "G_2") (pintype "passive"))
      (node (ref "Q9") (pin "9") (pinfunction "9_9") (pintype "passive"))
      (node (ref "R67") (pin "2") (pinfunction "2_2") (pintype "passive"))
    )
    (net (code "62") (name "Net-(Q13B-G)") (class "Default")
      (node (ref "Q13") (pin "4") (pinfunction "G_4") (pintype "passive"))
      (node (ref "Q9") (pin "11") (pinfunction "11_11") (pintype "passive"))
      (node (ref "R64") (pin "2") (pinfunction "2_2") (pintype "passive"))
    )
    (net (code "63") (name "Net-(U14A-1A)") (class "Default")
      (node (ref "R39") (pin "1") (pinfunction "1_1") (pintype "passive"))
      (node (ref "U14") (pin "1") (pinfunction "1A_1") (pintype "input"))
      (node (ref "U15") (pin "6") (pinfunction "OUTB_6") (pintype "passive"))
    )
    (net (code "64") (name "Net-(U14A-1Y)") (class "Default")
      (node (ref "R45") (pin "2") (pinfunction "2_2") (pintype "passive"))
      (node (ref "U14") (pin "11") (pinfunction "5A_11") (pintype "input"))
      (node (ref "U14") (pin "2") (pinfunction "1Y_2") (pintype "output"))
    )
    (net (code "65") (name "Net-(U14B-2A)") (class "Default")
      (node (ref "U14") (pin "3") (pinfunction "2A_3") (pintype "input"))
      (node (ref "U14") (pin "8") (pinfunction "4Y_8") (pintype "output"))
    )
    (net (code "66") (name "Net-(U14B-2Y)") (class "Default")
      (node (ref "U14") (pin "4") (pinfunction "2Y_4") (pintype "output"))
      (node (ref "U14") (pin "5") (pinfunction "3A_5") (pintype "input"))
      (node (ref "U15") (pin "7") (pinfunction "INA_7") (pintype "passive"))
    )
    (net (code "67") (name "Net-(U14C-3Y)") (class "Default")
      (node (ref "R33") (pin "2") (pinfunction "2_2") (pintype "passive"))
      (node (ref "U14") (pin "6") (pinfunction "3Y_6") (pintype "output"))
    )
    (net (code "68") (name "Net-(U16-A)") (class "Default")
      (node (ref "R38") (pin "1") (pinfunction "1_1") (pintype "passive"))
      (node (ref "R40") (pin "1") (pinfunction "1_1") (pintype "passive"))
      (node (ref "R44") (pin "2") (pinfunction "2_2") (pintype "passive"))
      (node (ref "U16") (pin "6") (pinfunction "A_6") (pintype "bidirectional"))
    )
    (net (code "69") (name "Net-(U16-B)") (class "Default")
      (node (ref "R34") (pin "1") (pinfunction "1_1") (pintype "passive"))
      (node (ref "R36") (pin "1") (pinfunction "1_1") (pintype "passive"))
      (node (ref "R38") (pin "2") (pinfunction "2_2") (pintype "passive"))
      (node (ref "U16") (pin "7") (pinfunction "B_7") (pintype "bidirectional"))
    )
    (net (code "70") (name "VCC_3.3V") (class "Default")
      (node (ref "C19") (pin "2") (pinfunction "2_2") (pintype "passive"))
      (node (ref "C22") (pin "2") (pinfunction "2_2") (pintype "passive"))
      (node (ref "C23") (pin "1") (pinfunction "1_1") (pintype "passive"))
      (node (ref "C26") (pin "2") (pinfunction "2_2") (pintype "passive"))
      (node (ref "R1") (pin "1") (pinfunction "1_1") (pintype "passive"))
      (node (ref "R2") (pin "1") (pinfunction "1_1") (pintype "passive"))
      (node (ref "R46") (pin "2") (pinfunction "2_2") (pintype "passive"))
      (node (ref "R55") (pin "1") (pinfunction "1_1") (pintype "passive"))
      (node (ref "R57") (pin "2") (pinfunction "2_2") (pintype "passive"))
      (node (ref "R60") (pin "1") (pinfunction "1_1") (pintype "passive"))
      (node (ref "R63") (pin "1") (pinfunction "1_1") (pintype "passive"))
      (node (ref "R66") (pin "1") (pinfunction "1_1") (pintype "passive"))
      (node (ref "R72") (pin "2") (pinfunction "2_2") (pintype "passive"))
      (node (ref "R74") (pin "2") (pinfunction "2_2") (pintype "passive"))
      (node (ref "R76") (pin "2") (pinfunction "2_2") (pintype "passive"))
      (node (ref "R78") (pin "2") (pinfunction "2_2") (pintype "passive"))
      (node (ref "U13") (pin "2") (pinfunction "3V3_2") (pintype "power_in"))
      (node (ref "U15") (pin "1") (pinfunction "VCC1_1") (pintype "passive"))
    )
    (net (code "71") (name "VCC_5V") (class "Default")
      (node (ref "P1") (pin "1") (pinfunction "1_1") (pintype "passive"))
    )
    (net (code "72") (name "VCC_24V") (class "Default")
      (node (ref "C32") (pin "2") (pinfunction "2_2") (pintype "passive"))
      (node (ref "JP3") (pin "4") (pinfunction "4_4") (pintype "passive"))
      (node (ref "JP3") (pin "5") (pinfunction "5_5") (pintype "passive"))
      (node (ref "R48") (pin "2") (pinfunction "2_2") (pintype "passive"))
      (node (ref "R58") (pin "2") (pinfunction "2_2") (pintype "passive"))
      (node (ref "R62") (pin "2") (pinfunction "2_2") (pintype "passive"))
      (node (ref "R65") (pin "2") (pinfunction "2_2") (pintype "passive"))
      (node (ref "R71") (pin "1") (pinfunction "1_1") (pintype "passive"))
      (node (ref "R73") (pin "1") (pinfunction "1_1") (pintype "passive"))
      (node (ref "R75") (pin "1") (pinfunction "1_1") (pintype "passive"))
      (node (ref "R77") (pin "1") (pinfunction "1_1") (pintype "passive"))
    )
    (net (code "73") (name "VCC_RS485_ISO") (class "Default")
      (node (ref "C18") (pin "2") (pinfunction "2_2") (pintype "passive"))
      (node (ref "C24") (pin "2") (pinfunction "2_2") (pintype "passive"))
      (node (ref "R35") (pin "2") (pinfunction "2_2") (pintype "passive"))
      (node (ref "R39") (pin "2") (pinfunction "2_2") (pintype "passive"))
      (node (ref "R44") (pin "1") (pinfunction "1_1") (pintype "passive"))
      (node (ref "U14") (pin "14") (pinfunction "VCC_14") (pintype "power_in"))
      (node (ref "U15") (pin "8") (pinfunction "VCC2_8") (pintype "passive"))
      (node (ref "U16") (pin "8") (pinfunction "VCC_8") (pintype "power_in"))
    )
    (net (code "74") (name "unconnected-(AN1-SIG-Pad1)") (class "Default")
      (node (ref "AN1") (pin "1") (pinfunction "SIG_1") (pintype "passive+no_connect"))
    )
    (net (code "75") (name "unconnected-(U13-NC-Pad32)") (class "Default")
      (node (ref "U13") (pin "32") (pinfunction "NC_32") (pintype "passive+no_connect"))
    )
    (net (code "76") (name "unconnected-(U13-SCK{slash}CLK*-Pad20)") (class "Default")
      (node (ref "U13") (pin "20") (pinfunction "SCK/CLK*_20") (pintype "bidirectional+no_connect"))
    )
    (net (code "77") (name "unconnected-(U13-SCS{slash}CMD*-Pad19)") (class "Default")
      (node (ref "U13") (pin "19") (pinfunction "SCS/CMD*_19") (pintype "bidirectional+no_connect"))
    )
    (net (code "78") (name "unconnected-(U13-SDI{slash}SD1*-Pad22)") (class "Default")
      (node (ref "U13") (pin "22") (pinfunction "SDI/SD1*_22") (pintype "bidirectional+no_connect"))
    )
    (net (code "79") (name "unconnected-(U13-SDO{slash}SD0*-Pad21)") (class "Default")
      (node (ref "U13") (pin "21") (pinfunction "SDO/SD0*_21") (pintype "bidirectional+no_connect"))
    )
    (net (code "80") (name "unconnected-(U13-SENSOR_VN-Pad5)") (class "Default")
      (node (ref "U13") (pin "5") (pinfunction "SENSOR_VN_5") (pintype "input+no_connect"))
    )
    (net (code "81") (name "unconnected-(U13-SENSOR_VP-Pad4)") (class "Default")
      (node (ref "U13") (pin "4") (pinfunction "SENSOR_VP_4") (pintype "input+no_connect"))
    )
    (net (code "82") (name "unconnected-(U13-SHD{slash}SD2*-Pad17)") (class "Default")
      (node (ref "U13") (pin "17") (pinfunction "SHD/SD2*_17") (pintype "bidirectional+no_connect"))
    )
    (net (code "83") (name "unconnected-(U13-SWP{slash}SD3*-Pad18)") (class "Default")
      (node (ref "U13") (pin "18") (pinfunction "SWP/SD3*_18") (pintype "bidirectional+no_connect"))
    )
  )
)
